# FPGA.net
KiCad netlist of a schematic drawn in Altium Designer
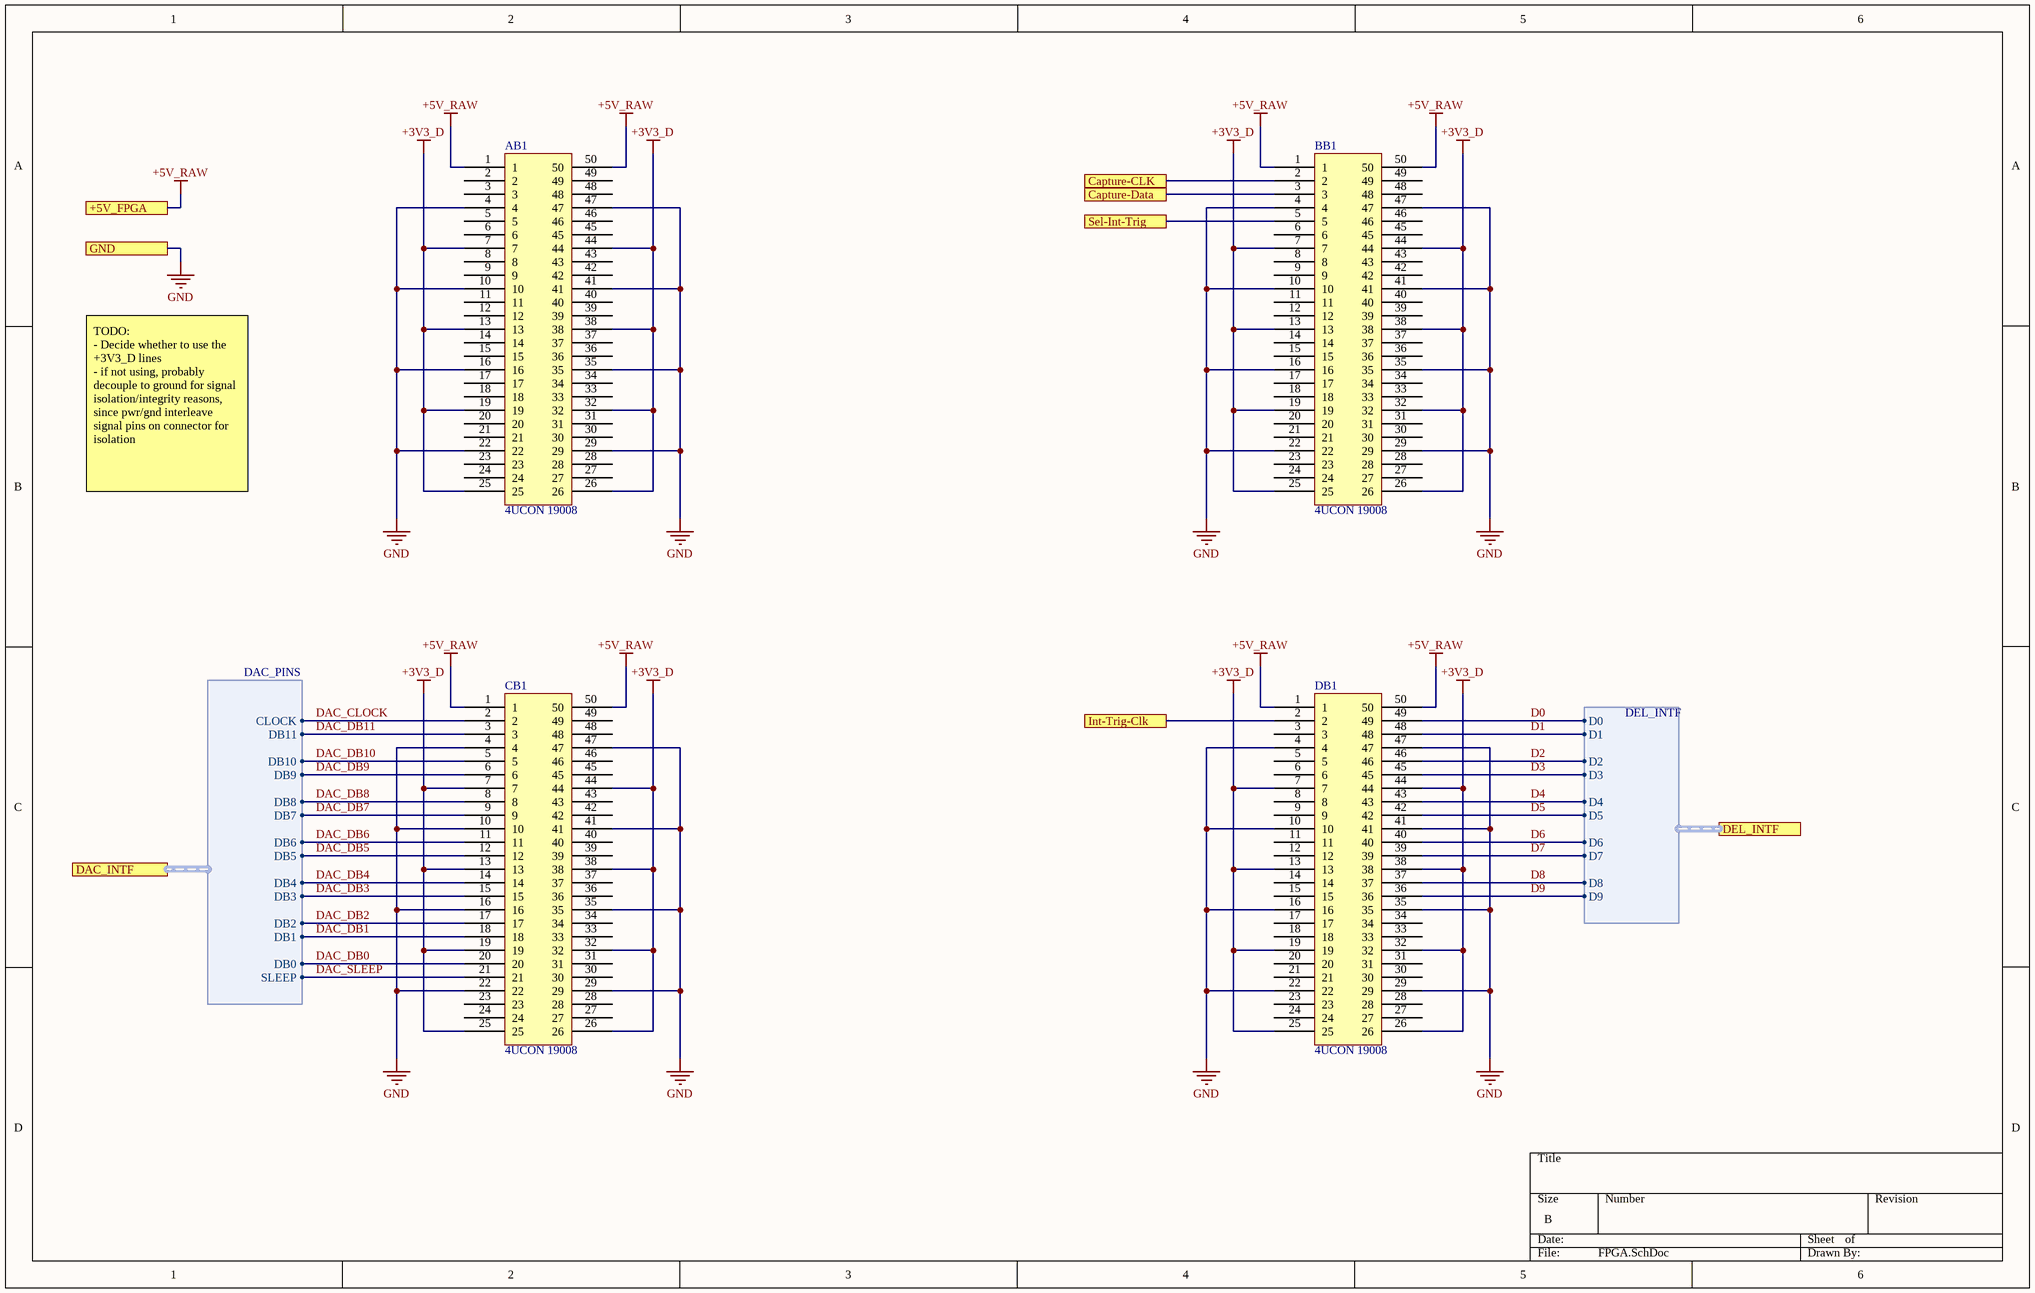
[diagram p0: FPGA.SchDoc]

(export (version "E")
  (design (tool "Eeschema 10.0.6"))
  (components
    (comp (ref "AB1")
      (value "4UCON 19008")
      (footprint "4UCON_19008")
      (libsource (lib "Local_Parts") (part "4UCON 19008"))
    )
    (comp (ref "BB1")
      (value "4UCON 19008")
      (footprint "4UCON_19008")
      (libsource (lib "Local_Parts") (part "4UCON 19008"))
    )
    (comp (ref "CB1")
      (value "4UCON 19008")
      (footprint "4UCON_19008")
      (libsource (lib "Local_Parts") (part "4UCON 19008"))
    )
    (comp (ref "DB1")
      (value "4UCON 19008")
      (footprint "4UCON_19008")
      (libsource (lib "Local_Parts") (part "4UCON 19008"))
    )
  )
  (nets
    (net (code "3") (name "+3V3_D") (class "Default")
      (node (ref "AB1") (pin "13") (pinfunction "13_13") (pintype "passive"))
      (node (ref "AB1") (pin "19") (pinfunction "19_19") (pintype "passive"))
      (node (ref "AB1") (pin "25") (pinfunction "25_25") (pintype "passive"))
      (node (ref "AB1") (pin "26") (pinfunction "26_26") (pintype "passive"))
      (node (ref "AB1") (pin "32") (pinfunction "32_32") (pintype "passive"))
      (node (ref "AB1") (pin "38") (pinfunction "38_38") (pintype "passive"))
      (node (ref "AB1") (pin "44") (pinfunction "44_44") (pintype "passive"))
      (node (ref "AB1") (pin "7") (pinfunction "7_7") (pintype "passive"))
      (node (ref "BB1") (pin "13") (pinfunction "13_13") (pintype "passive"))
      (node (ref "BB1") (pin "19") (pinfunction "19_19") (pintype "passive"))
      (node (ref "BB1") (pin "25") (pinfunction "25_25") (pintype "passive"))
      (node (ref "BB1") (pin "26") (pinfunction "26_26") (pintype "passive"))
      (node (ref "BB1") (pin "32") (pinfunction "32_32") (pintype "passive"))
      (node (ref "BB1") (pin "38") (pinfunction "38_38") (pintype "passive"))
      (node (ref "BB1") (pin "44") (pinfunction "44_44") (pintype "passive"))
      (node (ref "BB1") (pin "7") (pinfunction "7_7") (pintype "passive"))
      (node (ref "CB1") (pin "13") (pinfunction "13_13") (pintype "passive"))
      (node (ref "CB1") (pin "19") (pinfunction "19_19") (pintype "passive"))
      (node (ref "CB1") (pin "25") (pinfunction "25_25") (pintype "passive"))
      (node (ref "CB1") (pin "26") (pinfunction "26_26") (pintype "passive"))
      (node (ref "CB1") (pin "32") (pinfunction "32_32") (pintype "passive"))
      (node (ref "CB1") (pin "38") (pinfunction "38_38") (pintype "passive"))
      (node (ref "CB1") (pin "44") (pinfunction "44_44") (pintype "passive"))
      (node (ref "CB1") (pin "7") (pinfunction "7_7") (pintype "passive"))
      (node (ref "DB1") (pin "13") (pinfunction "13_13") (pintype "passive"))
      (node (ref "DB1") (pin "19") (pinfunction "19_19") (pintype "passive"))
      (node (ref "DB1") (pin "25") (pinfunction "25_25") (pintype "passive"))
      (node (ref "DB1") (pin "26") (pinfunction "26_26") (pintype "passive"))
      (node (ref "DB1") (pin "32") (pinfunction "32_32") (pintype "passive"))
      (node (ref "DB1") (pin "38") (pinfunction "38_38") (pintype "passive"))
      (node (ref "DB1") (pin "44") (pinfunction "44_44") (pintype "passive"))
      (node (ref "DB1") (pin "7") (pinfunction "7_7") (pintype "passive"))
    )
    (net (code "4") (name "+5V_RAW") (class "Default")
      (node (ref "AB1") (pin "1") (pinfunction "1_1") (pintype "passive"))
      (node (ref "AB1") (pin "50") (pinfunction "50_50") (pintype "passive"))
      (node (ref "BB1") (pin "1") (pinfunction "1_1") (pintype "passive"))
      (node (ref "BB1") (pin "50") (pinfunction "50_50") (pintype "passive"))
      (node (ref "CB1") (pin "1") (pinfunction "1_1") (pintype "passive"))
      (node (ref "CB1") (pin "50") (pinfunction "50_50") (pintype "passive"))
      (node (ref "DB1") (pin "1") (pinfunction "1_1") (pintype "passive"))
      (node (ref "DB1") (pin "50") (pinfunction "50_50") (pintype "passive"))
    )
    (net (code "5") (name "/Capture-CLK") (class "Default")
      (node (ref "BB1") (pin "2") (pinfunction "2_2") (pintype "passive"))
    )
    (net (code "6") (name "/Capture-Data") (class "Default")
      (node (ref "BB1") (pin "3") (pinfunction "3_3") (pintype "passive"))
    )
    (net (code "7") (name "/D0") (class "Default")
      (node (ref "DB1") (pin "49") (pinfunction "49_49") (pintype "passive"))
    )
    (net (code "8") (name "/D1") (class "Default")
      (node (ref "DB1") (pin "48") (pinfunction "48_48") (pintype "passive"))
    )
    (net (code "9") (name "/D2") (class "Default")
      (node (ref "DB1") (pin "46") (pinfunction "46_46") (pintype "passive"))
    )
    (net (code "10") (name "/D3") (class "Default")
      (node (ref "DB1") (pin "45") (pinfunction "45_45") (pintype "passive"))
    )
    (net (code "11") (name "/D4") (class "Default")
      (node (ref "DB1") (pin "43") (pinfunction "43_43") (pintype "passive"))
    )
    (net (code "12") (name "/D5") (class "Default")
      (node (ref "DB1") (pin "42") (pinfunction "42_42") (pintype "passive"))
    )
    (net (code "13") (name "/D6") (class "Default")
      (node (ref "DB1") (pin "40") (pinfunction "40_40") (pintype "passive"))
    )
    (net (code "14") (name "/D7") (class "Default")
      (node (ref "DB1") (pin "39") (pinfunction "39_39") (pintype "passive"))
    )
    (net (code "15") (name "/D8") (class "Default")
      (node (ref "DB1") (pin "37") (pinfunction "37_37") (pintype "passive"))
    )
    (net (code "16") (name "/D9") (class "Default")
      (node (ref "DB1") (pin "36") (pinfunction "36_36") (pintype "passive"))
    )
    (net (code "17") (name "/DAC_CLOCK") (class "Default")
      (node (ref "CB1") (pin "2") (pinfunction "2_2") (pintype "passive"))
    )
    (net (code "18") (name "/DAC_DB0") (class "Default")
      (node (ref "CB1") (pin "20") (pinfunction "20_20") (pintype "passive"))
    )
    (net (code "19") (name "/DAC_DB1") (class "Default")
      (node (ref "CB1") (pin "18") (pinfunction "18_18") (pintype "passive"))
    )
    (net (code "20") (name "/DAC_DB2") (class "Default")
      (node (ref "CB1") (pin "17") (pinfunction "17_17") (pintype "passive"))
    )
    (net (code "21") (name "/DAC_DB3") (class "Default")
      (node (ref "CB1") (pin "15") (pinfunction "15_15") (pintype "passive"))
    )
    (net (code "22") (name "/DAC_DB4") (class "Default")
      (node (ref "CB1") (pin "14") (pinfunction "14_14") (pintype "passive"))
    )
    (net (code "23") (name "/DAC_DB5") (class "Default")
      (node (ref "CB1") (pin "12") (pinfunction "12_12") (pintype "passive"))
    )
    (net (code "24") (name "/DAC_DB6") (class "Default")
      (node (ref "CB1") (pin "11") (pinfunction "11_11") (pintype "passive"))
    )
    (net (code "25") (name "/DAC_DB7") (class "Default")
      (node (ref "CB1") (pin "9") (pinfunction "9_9") (pintype "passive"))
    )
    (net (code "26") (name "/DAC_DB8") (class "Default")
      (node (ref "CB1") (pin "8") (pinfunction "8_8") (pintype "passive"))
    )
    (net (code "27") (name "/DAC_DB9") (class "Default")
      (node (ref "CB1") (pin "6") (pinfunction "6_6") (pintype "passive"))
    )
    (net (code "28") (name "/DAC_DB10") (class "Default")
      (node (ref "CB1") (pin "5") (pinfunction "5_5") (pintype "passive"))
    )
    (net (code "29") (name "/DAC_DB11") (class "Default")
      (node (ref "CB1") (pin "3") (pinfunction "3_3") (pintype "passive"))
    )
    (net (code "30") (name "/DAC_SLEEP") (class "Default")
      (node (ref "CB1") (pin "21") (pinfunction "21_21") (pintype "passive"))
    )
    (net (code "31") (name "/Int-Trig-Clk") (class "Default")
      (node (ref "DB1") (pin "2") (pinfunction "2_2") (pintype "passive"))
    )
    (net (code "32") (name "/Sel-Int-Trig") (class "Default")
      (node (ref "BB1") (pin "5") (pinfunction "5_5") (pintype "passive"))
    )
    (net (code "35") (name "GND") (class "Default")
      (node (ref "AB1") (pin "10") (pinfunction "10_10") (pintype "passive"))
      (node (ref "AB1") (pin "16") (pinfunction "16_16") (pintype "passive"))
      (node (ref "AB1") (pin "22") (pinfunction "22_22") (pintype "passive"))
      (node (ref "AB1") (pin "29") (pinfunction "29_29") (pintype "passive"))
      (node (ref "AB1") (pin "35") (pinfunction "35_35") (pintype "passive"))
      (node (ref "AB1") (pin "4") (pinfunction "4_4") (pintype "passive"))
      (node (ref "AB1") (pin "41") (pinfunction "41_41") (pintype "passive"))
      (node (ref "AB1") (pin "47") (pinfunction "47_47") (pintype "passive"))
      (node (ref "BB1") (pin "10") (pinfunction "10_10") (pintype "passive"))
      (node (ref "BB1") (pin "16") (pinfunction "16_16") (pintype "passive"))
      (node (ref "BB1") (pin "22") (pinfunction "22_22") (pintype "passive"))
      (node (ref "BB1") (pin "29") (pinfunction "29_29") (pintype "passive"))
      (node (ref "BB1") (pin "35") (pinfunction "35_35") (pintype "passive"))
      (node (ref "BB1") (pin "4") (pinfunction "4_4") (pintype "passive"))
      (node (ref "BB1") (pin "41") (pinfunction "41_41") (pintype "passive"))
      (node (ref "BB1") (pin "47") (pinfunction "47_47") (pintype "passive"))
      (node (ref "CB1") (pin "10") (pinfunction "10_10") (pintype "passive"))
      (node (ref "CB1") (pin "16") (pinfunction "16_16") (pintype "passive"))
      (node (ref "CB1") (pin "22") (pinfunction "22_22") (pintype "passive"))
      (node (ref "CB1") (pin "29") (pinfunction "29_29") (pintype "passive"))
      (node (ref "CB1") (pin "35") (pinfunction "35_35") (pintype "passive"))
      (node (ref "CB1") (pin "4") (pinfunction "4_4") (pintype "passive"))
      (node (ref "CB1") (pin "41") (pinfunction "41_41") (pintype "passive"))
      (node (ref "CB1") (pin "47") (pinfunction "47_47") (pintype "passive"))
      (node (ref "DB1") (pin "10") (pinfunction "10_10") (pintype "passive"))
      (node (ref "DB1") (pin "16") (pinfunction "16_16") (pintype "passive"))
      (node (ref "DB1") (pin "22") (pinfunction "22_22") (pintype "passive"))
      (node (ref "DB1") (pin "29") (pinfunction "29_29") (pintype "passive"))
      (node (ref "DB1") (pin "35") (pinfunction "35_35") (pintype "passive"))
      (node (ref "DB1") (pin "4") (pinfunction "4_4") (pintype "passive"))
      (node (ref "DB1") (pin "41") (pinfunction "41_41") (pintype "passive"))
      (node (ref "DB1") (pin "47") (pinfunction "47_47") (pintype "passive"))
    )
    (net (code "36") (name "unconnected-(AB1-Pad2)") (class "Default")
      (node (ref "AB1") (pin "2") (pinfunction "2_2") (pintype "passive"))
    )
    (net (code "37") (name "unconnected-(AB1-Pad3)") (class "Default")
      (node (ref "AB1") (pin "3") (pinfunction "3_3") (pintype "passive"))
    )
    (net (code "38") (name "unconnected-(AB1-Pad5)") (class "Default")
      (node (ref "AB1") (pin "5") (pinfunction "5_5") (pintype "passive"))
    )
    (net (code "39") (name "unconnected-(AB1-Pad6)") (class "Default")
      (node (ref "AB1") (pin "6") (pinfunction "6_6") (pintype "passive"))
    )
    (net (code "40") (name "unconnected-(AB1-Pad8)") (class "Default")
      (node (ref "AB1") (pin "8") (pinfunction "8_8") (pintype "passive"))
    )
    (net (code "41") (name "unconnected-(AB1-Pad9)") (class "Default")
      (node (ref "AB1") (pin "9") (pinfunction "9_9") (pintype "passive"))
    )
    (net (code "42") (name "unconnected-(AB1-Pad11)") (class "Default")
      (node (ref "AB1") (pin "11") (pinfunction "11_11") (pintype "passive"))
    )
    (net (code "43") (name "unconnected-(AB1-Pad12)") (class "Default")
      (node (ref "AB1") (pin "12") (pinfunction "12_12") (pintype "passive"))
    )
    (net (code "44") (name "unconnected-(AB1-Pad14)") (class "Default")
      (node (ref "AB1") (pin "14") (pinfunction "14_14") (pintype "passive"))
    )
    (net (code "45") (name "unconnected-(AB1-Pad15)") (class "Default")
      (node (ref "AB1") (pin "15") (pinfunction "15_15") (pintype "passive"))
    )
    (net (code "46") (name "unconnected-(AB1-Pad17)") (class "Default")
      (node (ref "AB1") (pin "17") (pinfunction "17_17") (pintype "passive"))
    )
    (net (code "47") (name "unconnected-(AB1-Pad18)") (class "Default")
      (node (ref "AB1") (pin "18") (pinfunction "18_18") (pintype "passive"))
    )
    (net (code "48") (name "unconnected-(AB1-Pad20)") (class "Default")
      (node (ref "AB1") (pin "20") (pinfunction "20_20") (pintype "passive"))
    )
    (net (code "49") (name "unconnected-(AB1-Pad21)") (class "Default")
      (node (ref "AB1") (pin "21") (pinfunction "21_21") (pintype "passive"))
    )
    (net (code "50") (name "unconnected-(AB1-Pad23)") (class "Default")
      (node (ref "AB1") (pin "23") (pinfunction "23_23") (pintype "passive"))
    )
    (net (code "51") (name "unconnected-(AB1-Pad24)") (class "Default")
      (node (ref "AB1") (pin "24") (pinfunction "24_24") (pintype "passive"))
    )
    (net (code "52") (name "unconnected-(AB1-Pad27)") (class "Default")
      (node (ref "AB1") (pin "27") (pinfunction "27_27") (pintype "passive"))
    )
    (net (code "53") (name "unconnected-(AB1-Pad28)") (class "Default")
      (node (ref "AB1") (pin "28") (pinfunction "28_28") (pintype "passive"))
    )
    (net (code "54") (name "unconnected-(AB1-Pad30)") (class "Default")
      (node (ref "AB1") (pin "30") (pinfunction "30_30") (pintype "passive"))
    )
    (net (code "55") (name "unconnected-(AB1-Pad31)") (class "Default")
      (node (ref "AB1") (pin "31") (pinfunction "31_31") (pintype "passive"))
    )
    (net (code "56") (name "unconnected-(AB1-Pad33)") (class "Default")
      (node (ref "AB1") (pin "33") (pinfunction "33_33") (pintype "passive"))
    )
    (net (code "57") (name "unconnected-(AB1-Pad34)") (class "Default")
      (node (ref "AB1") (pin "34") (pinfunction "34_34") (pintype "passive"))
    )
    (net (code "58") (name "unconnected-(AB1-Pad36)") (class "Default")
      (node (ref "AB1") (pin "36") (pinfunction "36_36") (pintype "passive"))
    )
    (net (code "59") (name "unconnected-(AB1-Pad37)") (class "Default")
      (node (ref "AB1") (pin "37") (pinfunction "37_37") (pintype "passive"))
    )
    (net (code "60") (name "unconnected-(AB1-Pad39)") (class "Default")
      (node (ref "AB1") (pin "39") (pinfunction "39_39") (pintype "passive"))
    )
    (net (code "61") (name "unconnected-(AB1-Pad40)") (class "Default")
      (node (ref "AB1") (pin "40") (pinfunction "40_40") (pintype "passive"))
    )
    (net (code "62") (name "unconnected-(AB1-Pad42)") (class "Default")
      (node (ref "AB1") (pin "42") (pinfunction "42_42") (pintype "passive"))
    )
    (net (code "63") (name "unconnected-(AB1-Pad43)") (class "Default")
      (node (ref "AB1") (pin "43") (pinfunction "43_43") (pintype "passive"))
    )
    (net (code "64") (name "unconnected-(AB1-Pad45)") (class "Default")
      (node (ref "AB1") (pin "45") (pinfunction "45_45") (pintype "passive"))
    )
    (net (code "65") (name "unconnected-(AB1-Pad46)") (class "Default")
      (node (ref "AB1") (pin "46") (pinfunction "46_46") (pintype "passive"))
    )
    (net (code "66") (name "unconnected-(AB1-Pad48)") (class "Default")
      (node (ref "AB1") (pin "48") (pinfunction "48_48") (pintype "passive"))
    )
    (net (code "67") (name "unconnected-(AB1-Pad49)") (class "Default")
      (node (ref "AB1") (pin "49") (pinfunction "49_49") (pintype "passive"))
    )
    (net (code "68") (name "unconnected-(BB1-Pad6)") (class "Default")
      (node (ref "BB1") (pin "6") (pinfunction "6_6") (pintype "passive"))
    )
    (net (code "69") (name "unconnected-(BB1-Pad8)") (class "Default")
      (node (ref "BB1") (pin "8") (pinfunction "8_8") (pintype "passive"))
    )
    (net (code "70") (name "unconnected-(BB1-Pad9)") (class "Default")
      (node (ref "BB1") (pin "9") (pinfunction "9_9") (pintype "passive"))
    )
    (net (code "71") (name "unconnected-(BB1-Pad11)") (class "Default")
      (node (ref "BB1") (pin "11") (pinfunction "11_11") (pintype "passive"))
    )
    (net (code "72") (name "unconnected-(BB1-Pad12)") (class "Default")
      (node (ref "BB1") (pin "12") (pinfunction "12_12") (pintype "passive"))
    )
    (net (code "73") (name "unconnected-(BB1-Pad14)") (class "Default")
      (node (ref "BB1") (pin "14") (pinfunction "14_14") (pintype "passive"))
    )
    (net (code "74") (name "unconnected-(BB1-Pad15)") (class "Default")
      (node (ref "BB1") (pin "15") (pinfunction "15_15") (pintype "passive"))
    )
    (net (code "75") (name "unconnected-(BB1-Pad17)") (class "Default")
      (node (ref "BB1") (pin "17") (pinfunction "17_17") (pintype "passive"))
    )
    (net (code "76") (name "unconnected-(BB1-Pad18)") (class "Default")
      (node (ref "BB1") (pin "18") (pinfunction "18_18") (pintype "passive"))
    )
    (net (code "77") (name "unconnected-(BB1-Pad20)") (class "Default")
      (node (ref "BB1") (pin "20") (pinfunction "20_20") (pintype "passive"))
    )
    (net (code "78") (name "unconnected-(BB1-Pad21)") (class "Default")
      (node (ref "BB1") (pin "21") (pinfunction "21_21") (pintype "passive"))
    )
    (net (code "79") (name "unconnected-(BB1-Pad23)") (class "Default")
      (node (ref "BB1") (pin "23") (pinfunction "23_23") (pintype "passive"))
    )
    (net (code "80") (name "unconnected-(BB1-Pad24)") (class "Default")
      (node (ref "BB1") (pin "24") (pinfunction "24_24") (pintype "passive"))
    )
    (net (code "81") (name "unconnected-(BB1-Pad27)") (class "Default")
      (node (ref "BB1") (pin "27") (pinfunction "27_27") (pintype "passive"))
    )
    (net (code "82") (name "unconnected-(BB1-Pad28)") (class "Default")
      (node (ref "BB1") (pin "28") (pinfunction "28_28") (pintype "passive"))
    )
    (net (code "83") (name "unconnected-(BB1-Pad30)") (class "Default")
      (node (ref "BB1") (pin "30") (pinfunction "30_30") (pintype "passive"))
    )
    (net (code "84") (name "unconnected-(BB1-Pad31)") (class "Default")
      (node (ref "BB1") (pin "31") (pinfunction "31_31") (pintype "passive"))
    )
    (net (code "85") (name "unconnected-(BB1-Pad33)") (class "Default")
      (node (ref "BB1") (pin "33") (pinfunction "33_33") (pintype "passive"))
    )
    (net (code "86") (name "unconnected-(BB1-Pad34)") (class "Default")
      (node (ref "BB1") (pin "34") (pinfunction "34_34") (pintype "passive"))
    )
    (net (code "87") (name "unconnected-(BB1-Pad36)") (class "Default")
      (node (ref "BB1") (pin "36") (pinfunction "36_36") (pintype "passive"))
    )
    (net (code "88") (name "unconnected-(BB1-Pad37)") (class "Default")
      (node (ref "BB1") (pin "37") (pinfunction "37_37") (pintype "passive"))
    )
    (net (code "89") (name "unconnected-(BB1-Pad39)") (class "Default")
      (node (ref "BB1") (pin "39") (pinfunction "39_39") (pintype "passive"))
    )
    (net (code "90") (name "unconnected-(BB1-Pad40)") (class "Default")
      (node (ref "BB1") (pin "40") (pinfunction "40_40") (pintype "passive"))
    )
    (net (code "91") (name "unconnected-(BB1-Pad42)") (class "Default")
      (node (ref "BB1") (pin "42") (pinfunction "42_42") (pintype "passive"))
    )
    (net (code "92") (name "unconnected-(BB1-Pad43)") (class "Default")
      (node (ref "BB1") (pin "43") (pinfunction "43_43") (pintype "passive"))
    )
    (net (code "93") (name "unconnected-(BB1-Pad45)") (class "Default")
      (node (ref "BB1") (pin "45") (pinfunction "45_45") (pintype "passive"))
    )
    (net (code "94") (name "unconnected-(BB1-Pad46)") (class "Default")
      (node (ref "BB1") (pin "46") (pinfunction "46_46") (pintype "passive"))
    )
    (net (code "95") (name "unconnected-(BB1-Pad48)") (class "Default")
      (node (ref "BB1") (pin "48") (pinfunction "48_48") (pintype "passive"))
    )
    (net (code "96") (name "unconnected-(BB1-Pad49)") (class "Default")
      (node (ref "BB1") (pin "49") (pinfunction "49_49") (pintype "passive"))
    )
    (net (code "97") (name "unconnected-(CB1-Pad23)") (class "Default")
      (node (ref "CB1") (pin "23") (pinfunction "23_23") (pintype "passive"))
    )
    (net (code "98") (name "unconnected-(CB1-Pad24)") (class "Default")
      (node (ref "CB1") (pin "24") (pinfunction "24_24") (pintype "passive"))
    )
    (net (code "99") (name "unconnected-(CB1-Pad27)") (class "Default")
      (node (ref "CB1") (pin "27") (pinfunction "27_27") (pintype "passive"))
    )
    (net (code "100") (name "unconnected-(CB1-Pad28)") (class "Default")
      (node (ref "CB1") (pin "28") (pinfunction "28_28") (pintype "passive"))
    )
    (net (code "101") (name "unconnected-(CB1-Pad30)") (class "Default")
      (node (ref "CB1") (pin "30") (pinfunction "30_30") (pintype "passive"))
    )
    (net (code "102") (name "unconnected-(CB1-Pad31)") (class "Default")
      (node (ref "CB1") (pin "31") (pinfunction "31_31") (pintype "passive"))
    )
    (net (code "103") (name "unconnected-(CB1-Pad33)") (class "Default")
      (node (ref "CB1") (pin "33") (pinfunction "33_33") (pintype "passive"))
    )
    (net (code "104") (name "unconnected-(CB1-Pad34)") (class "Default")
      (node (ref "CB1") (pin "34") (pinfunction "34_34") (pintype "passive"))
    )
    (net (code "105") (name "unconnected-(CB1-Pad36)") (class "Default")
      (node (ref "CB1") (pin "36") (pinfunction "36_36") (pintype "passive"))
    )
    (net (code "106") (name "unconnected-(CB1-Pad37)") (class "Default")
      (node (ref "CB1") (pin "37") (pinfunction "37_37") (pintype "passive"))
    )
    (net (code "107") (name "unconnected-(CB1-Pad39)") (class "Default")
      (node (ref "CB1") (pin "39") (pinfunction "39_39") (pintype "passive"))
    )
    (net (code "108") (name "unconnected-(CB1-Pad40)") (class "Default")
      (node (ref "CB1") (pin "40") (pinfunction "40_40") (pintype "passive"))
    )
    (net (code "109") (name "unconnected-(CB1-Pad42)") (class "Default")
      (node (ref "CB1") (pin "42") (pinfunction "42_42") (pintype "passive"))
    )
    (net (code "110") (name "unconnected-(CB1-Pad43)") (class "Default")
      (node (ref "CB1") (pin "43") (pinfunction "43_43") (pintype "passive"))
    )
    (net (code "111") (name "unconnected-(CB1-Pad45)") (class "Default")
      (node (ref "CB1") (pin "45") (pinfunction "45_45") (pintype "passive"))
    )
    (net (code "112") (name "unconnected-(CB1-Pad46)") (class "Default")
      (node (ref "CB1") (pin "46") (pinfunction "46_46") (pintype "passive"))
    )
    (net (code "113") (name "unconnected-(CB1-Pad48)") (class "Default")
      (node (ref "CB1") (pin "48") (pinfunction "48_48") (pintype "passive"))
    )
    (net (code "114") (name "unconnected-(CB1-Pad49)") (class "Default")
      (node (ref "CB1") (pin "49") (pinfunction "49_49") (pintype "passive"))
    )
    (net (code "115") (name "unconnected-(DB1-Pad3)") (class "Default")
      (node (ref "DB1") (pin "3") (pinfunction "3_3") (pintype "passive"))
    )
    (net (code "116") (name "unconnected-(DB1-Pad5)") (class "Default")
      (node (ref "DB1") (pin "5") (pinfunction "5_5") (pintype "passive"))
    )
    (net (code "117") (name "unconnected-(DB1-Pad6)") (class "Default")
      (node (ref "DB1") (pin "6") (pinfunction "6_6") (pintype "passive"))
    )
    (net (code "118") (name "unconnected-(DB1-Pad8)") (class "Default")
      (node (ref "DB1") (pin "8") (pinfunction "8_8") (pintype "passive"))
    )
    (net (code "119") (name "unconnected-(DB1-Pad9)") (class "Default")
      (node (ref "DB1") (pin "9") (pinfunction "9_9") (pintype "passive"))
    )
    (net (code "120") (name "unconnected-(DB1-Pad11)") (class "Default")
      (node (ref "DB1") (pin "11") (pinfunction "11_11") (pintype "passive"))
    )
    (net (code "121") (name "unconnected-(DB1-Pad12)") (class "Default")
      (node (ref "DB1") (pin "12") (pinfunction "12_12") (pintype "passive"))
    )
    (net (code "122") (name "unconnected-(DB1-Pad14)") (class "Default")
      (node (ref "DB1") (pin "14") (pinfunction "14_14") (pintype "passive"))
    )
    (net (code "123") (name "unconnected-(DB1-Pad15)") (class "Default")
      (node (ref "DB1") (pin "15") (pinfunction "15_15") (pintype "passive"))
    )
    (net (code "124") (name "unconnected-(DB1-Pad17)") (class "Default")
      (node (ref "DB1") (pin "17") (pinfunction "17_17") (pintype "passive"))
    )
    (net (code "125") (name "unconnected-(DB1-Pad18)") (class "Default")
      (node (ref "DB1") (pin "18") (pinfunction "18_18") (pintype "passive"))
    )
    (net (code "126") (name "unconnected-(DB1-Pad20)") (class "Default")
      (node (ref "DB1") (pin "20") (pinfunction "20_20") (pintype "passive"))
    )
    (net (code "127") (name "unconnected-(DB1-Pad21)") (class "Default")
      (node (ref "DB1") (pin "21") (pinfunction "21_21") (pintype "passive"))
    )
    (net (code "128") (name "unconnected-(DB1-Pad23)") (class "Default")
      (node (ref "DB1") (pin "23") (pinfunction "23_23") (pintype "passive"))
    )
    (net (code "129") (name "unconnected-(DB1-Pad24)") (class "Default")
      (node (ref "DB1") (pin "24") (pinfunction "24_24") (pintype "passive"))
    )
    (net (code "130") (name "unconnected-(DB1-Pad27)") (class "Default")
      (node (ref "DB1") (pin "27") (pinfunction "27_27") (pintype "passive"))
    )
    (net (code "131") (name "unconnected-(DB1-Pad28)") (class "Default")
      (node (ref "DB1") (pin "28") (pinfunction "28_28") (pintype "passive"))
    )
    (net (code "132") (name "unconnected-(DB1-Pad30)") (class "Default")
      (node (ref "DB1") (pin "30") (pinfunction "30_30") (pintype "passive"))
    )
    (net (code "133") (name "unconnected-(DB1-Pad31)") (class "Default")
      (node (ref "DB1") (pin "31") (pinfunction "31_31") (pintype "passive"))
    )
    (net (code "134") (name "unconnected-(DB1-Pad33)") (class "Default")
      (node (ref "DB1") (pin "33") (pinfunction "33_33") (pintype "passive"))
    )
    (net (code "135") (name "unconnected-(DB1-Pad34)") (class "Default")
      (node (ref "DB1") (pin "34") (pinfunction "34_34") (pintype "passive"))
    )
  )
)
